# Flash.net
KiCad netlist of a schematic drawn in Altium Designer
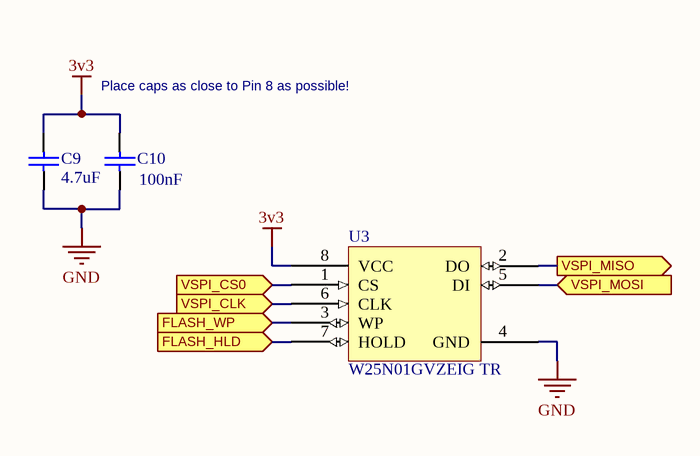
[diagram p0: Flash.SchDoc]

(export (version "E")
  (design (tool "Eeschema 10.0.6"))
  (components
    (comp (ref "C9")
      (value "GRM155R60J475ME87D")
      (footprint "Capacitor_0402")
      (description "6.3V 4.7uF X5R ±20% 0402 Multilayer Ceramic Capacitors MLCC - SMD/SMT ROHS")
      (fields (field (name "CAPACITANCE") "4.7uF") (field (name "TOLERANCE") "20%"))
      (libsource (lib "RIT Launch Initiative") (part "CAPACITOR"))
    )
    (comp (ref "C10")
      (value "GRM155R71E104KE14D")
      (footprint "Capacitor_0402")
      (description "Chip Capacitor 100nF 0402 25V X7R")
      (fields (field (name "CAPACITANCE") "100nF"))
      (libsource (lib "RIT Launch Initiative") (part "CAPACITOR"))
    )
    (comp (ref "U3")
      (value "W25N01GVZEIG TR")
      (footprint "W25N01GVZEIG TR-Footprint-1")
      (description "1Gb NAND Flash Memory With dual/Quad SPI And Continuous Read")
      (libsource (lib "RIT Launch Initiative") (part "W25N01GVZEIG TR-Symbol-1"))
    )
  )
  (nets
    (net (code "1") (name "/FLASH_HLD") (class "Default")
      (node (ref "U3") (pin "7") (pinfunction "HOLD_7") (pintype "bidirectional"))
    )
    (net (code "2") (name "/FLASH_WP") (class "Default")
      (node (ref "U3") (pin "3") (pinfunction "WP_3") (pintype "bidirectional"))
    )
    (net (code "3") (name "/VSPI_CLK") (class "Default")
      (node (ref "U3") (pin "6") (pinfunction "CLK_6") (pintype "input"))
    )
    (net (code "4") (name "/VSPI_CS0") (class "Default")
      (node (ref "U3") (pin "1") (pinfunction "CS_1") (pintype "input"))
    )
    (net (code "5") (name "/VSPI_MISO") (class "Default")
      (node (ref "U3") (pin "2") (pinfunction "DO_2") (pintype "bidirectional"))
    )
    (net (code "6") (name "/VSPI_MOSI") (class "Default")
      (node (ref "U3") (pin "5") (pinfunction "DI_5") (pintype "bidirectional"))
    )
    (net (code "7") (name "3v3") (class "Default")
      (node (ref "C10") (pin "2") (pinfunction "2_2") (pintype "passive"))
      (node (ref "C9") (pin "2") (pinfunction "2_2") (pintype "passive"))
      (node (ref "U3") (pin "8") (pinfunction "VCC_8") (pintype "power_in"))
    )
    (net (code "8") (name "GND") (class "Default")
      (node (ref "C10") (pin "1") (pinfunction "1_1") (pintype "passive"))
      (node (ref "C9") (pin "1") (pinfunction "1_1") (pintype "passive"))
      (node (ref "U3") (pin "4") (pinfunction "GND_4") (pintype "power_in"))
    )
  )
)
